# USB.net
KiCad netlist of a schematic drawn in Altium Designer
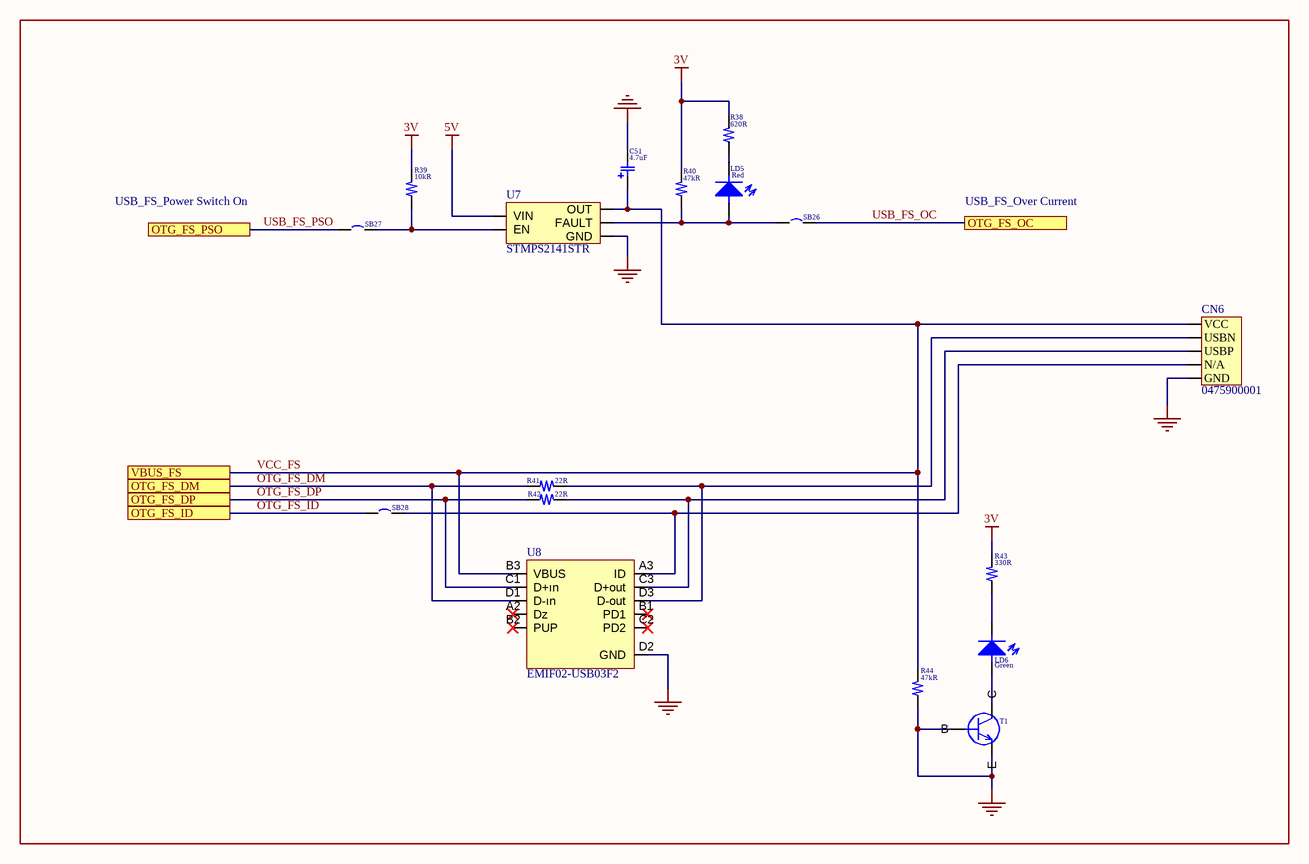
[diagram p0: USB.SchDoc]

(export (version "E")
  (design (tool "Eeschema 10.0.6"))
  (components
    (comp (ref "C51")
      (value "4.7uF")
      (footprint "CAP-TANT")
      (description "Cap Tant Polymer 4.7uF 10V K CASE 20% (3.2 x 1.6 x 1mm) SMD 300m Ohm 105°C T/R")
      (fields
        (field (name "MANUFACTURER") "Kyocera AVX")
        (field (name "MANUFACTURER PART NUMBER") "TCJK475M010R0300E")
      )
      (libsource (lib "STM32") (part "C-TANT POLY 4.7UF 10V 1206"))
    )
    (comp (ref "CN6")
      (value "0475900001")
      (footprint "USB MİCRO A")
      (description "USB Connector, 5 Contact(s), Female, Right Angle, Surface Mount Terminal, Locking, Receptacle")
      (fields (field (name "MANUFACTURER") "Molex") (field (name "MANUFACTURER PART NUMBER") "47590-0001"))
      (libsource (lib "STM32") (part "CONN USB MİCRO A 5P"))
    )
    (comp (ref "LD5")
      (value "150060RS75000")
      (footprint "LED-RED-0603")
      (description "LED Low-Power Uni-Color Red 630nm 2V 2-Pin Chip 0603(1608Metric) T/R")
      (fields (field (name "MANUFACTURER") "Wurth Electronics") (field (name "COLOR") "Red"))
      (libsource (lib "STM32") (part "LED RED CLEAR 0603 SMD"))
    )
    (comp (ref "LD6")
      (value "150060VS75000")
      (footprint "LED-GREEN-0603")
      (description "WURTH ELEKTRONIK - 150060VS75000 - LED, Green, SMD, 0603, 30 mA, 2 V, 570 nm")
      (fields (field (name "MANUFACTURER") "Wurth Electronics") (field (name "COLOR") "Green"))
      (libsource (lib "STM32") (part "LED GREEN CLEAR 0603 SMD"))
    )
    (comp (ref "R38")
      (value "620R")
      (footprint "RES-0603")
      (description "SMD Chip Resistor, 620 Ohm, ± 1%, 100 mW, 0603 [1608 Metric], Thick Film, General Purpose")
      (fields
        (field (name "MANUFACTURER") "Yageo")
        (field (name "MANUFACTURER PART NUMBER") "RC0603FR-07620RL")
      )
      (libsource (lib "STM32") (part "RES 620 OHM 1% 1/10W 0603"))
    )
    (comp (ref "R39")
      (value "10kR")
      (footprint "RES-0402")
      (description "SMD Chip Resistor, 10 kOhm, ± 1%, 63 mW, 0402 [1005 Metric], Thick Film, General Purpose")
      (fields
        (field (name "MANUFACTURER") "Yageo")
        (field (name "MANUFACTURER PART NUMBER") "RC0402FR-0710KL")
      )
      (libsource (lib "STM32") (part "RES 10K OHM 1% 1/16W 0402"))
    )
    (comp (ref "R40")
      (value "47kR")
      (footprint "RES-0402")
      (description "SMD Chip Resistor, 47 kOhm, ± 1%, 63 mW, 0402 [1005 Metric], Thick Film, General Purpose")
      (fields
        (field (name "MANUFACTURER") "Yageo")
        (field (name "MANUFACTURER PART NUMBER") "RC0402FR-0747KL")
      )
      (libsource (lib "STM32") (part "RES 47K OHM 1% 1/16W 0402"))
    )
    (comp (ref "R41")
      (value "22R")
      (footprint "RES-0603")
      (description "SMD Chip Resistor, 22 Ohm, ± 1%, 100 mW, 0603 [1608 Metric], Thick Film, General Purpose")
      (fields
        (field (name "MANUFACTURER") "Yageo")
        (field (name "MANUFACTURER PART NUMBER") "RC0603FR-0722RL")
      )
      (libsource (lib "STM32") (part "RES 22 OHM 1% 1/10W 0603"))
    )
    (comp (ref "R42")
      (value "22R")
      (footprint "RES-0603")
      (description "SMD Chip Resistor, 22 Ohm, ± 1%, 100 mW, 0603 [1608 Metric], Thick Film, General Purpose")
      (fields
        (field (name "MANUFACTURER") "Yageo")
        (field (name "MANUFACTURER PART NUMBER") "RC0603FR-0722RL")
      )
      (libsource (lib "STM32") (part "RES 22 OHM 1% 1/10W 0603"))
    )
    (comp (ref "R43")
      (value "330R")
      (footprint "RES-0402")
      (description "SMD Chip Resistor, 330 Ohm, ± 1%, 63 mW, 0402 [1005 Metric], Thick Film, General Purpose")
      (fields
        (field (name "MANUFACTURER") "Yageo")
        (field (name "MANUFACTURER PART NUMBER") "RC0402FR-07330RL")
      )
      (libsource (lib "STM32") (part "RES 330 OHM 1% 1/16W 0402"))
    )
    (comp (ref "R44")
      (value "47kR")
      (footprint "RES-0402")
      (description "SMD Chip Resistor, 47 kOhm, ± 1%, 63 mW, 0402 [1005 Metric], Thick Film, General Purpose")
      (fields
        (field (name "MANUFACTURER") "Yageo")
        (field (name "MANUFACTURER PART NUMBER") "RC0402FR-0747KL")
      )
      (libsource (lib "STM32") (part "RES 47K OHM 1% 1/16W 0402"))
    )
    (comp (ref "SB26")
      (value "RC0402JR-070RL")
      (footprint "RES-0402")
      (description "Zero Ohm Resistor, Jumper, 0402 [1005 Metric], Thick Film, 62.5 mW, 1 A, Surface Mount")
      (fields
        (field (name "MANUFACTURER") "Yageo")
        (field (name "MANUFACTURER PART NUMBER") "RC0603JR-070RL")
      )
      (libsource (lib "STM32") (part "RES 0 OHM JUMPER 1/10W 0603"))
    )
    (comp (ref "SB27")
      (value "RC0402JR-070RL")
      (footprint "RES-0402")
      (description "Zero Ohm Resistor, Jumper, 0402 [1005 Metric], Thick Film, 62.5 mW, 1 A, Surface Mount")
      (fields
        (field (name "MANUFACTURER") "Yageo")
        (field (name "MANUFACTURER PART NUMBER") "RC0603JR-070RL")
      )
      (libsource (lib "STM32") (part "RES 0 OHM JUMPER 1/10W 0603"))
    )
    (comp (ref "SB28")
      (value "RC0402JR-070RL")
      (footprint "RES-0402")
      (description "Zero Ohm Resistor, Jumper, 0402 [1005 Metric], Thick Film, 62.5 mW, 1 A, Surface Mount")
      (fields
        (field (name "MANUFACTURER") "Yageo")
        (field (name "MANUFACTURER PART NUMBER") "RC0603JR-070RL")
      )
      (libsource (lib "STM32") (part "RES 0 OHM JUMPER 1/10W 0603"))
    )
    (comp (ref "T1")
      (value "MMBT2222ALT1G")
      (footprint "SOT23-3")
      (description "Bipolar (BJT) Transistor NPN 40V 600mA 300MHz 225mW Surface Mount SOT-23-3")
      (fields (field (name "MANUFACTURER") "ON Semiconductor"))
      (libsource (lib "STM32") (part "TRANS NPN 40V 0.6A SOT23-3"))
    )
    (comp (ref "U7")
      (value "STMPS2141STR")
      (footprint "SOT23-5L")
      (description "STMPS Series 1 Channel 5.5 V 500 mA 200 mOhm High Side Power Switch - SOT-23-5")
      (fields (field (name "MANUFACTURER") "STMicroelectronics"))
      (libsource (lib "STM32") (part "IC PWR SWITCH N-CHAN 1{colon}1 SOT23-5"))
    )
    (comp (ref "U8")
      (value "EMIF02-USB03F2")
      (footprint "Flip-Chip-11")
      (description "2-line EMI filter and ESD protection with R pull-up for USB interfaces")
      (fields (field (name "MANUFACTURER") "STMicroelectronics"))
      (libsource (lib "STM32") (part "FILTER RC(PI) 33 OHM/20PF SMD"))
    )
  )
  (nets
    (net (code "1") (name "/OTG_FS_DM") (class "Default")
      (node (ref "R41") (pin "1") (pinfunction "1_1") (pintype "passive"))
      (node (ref "U8") (pin "D1") (pinfunction "D-ın_D1") (pintype "passive"))
    )
    (net (code "2") (name "/OTG_FS_DP") (class "Default")
      (node (ref "R42") (pin "1") (pinfunction "1_1") (pintype "passive"))
      (node (ref "U8") (pin "C1") (pinfunction "D+ın_C1") (pintype "passive"))
    )
    (net (code "3") (name "/OTG_FS_ID") (class "Default")
      (node (ref "SB28") (pin "1") (pinfunction "1_1") (pintype "passive"))
    )
    (net (code "4") (name "/USB_FS_OC") (class "Default")
      (node (ref "SB26") (pin "2") (pinfunction "2_2") (pintype "passive"))
    )
    (net (code "5") (name "/USB_FS_PSO") (class "Default")
      (node (ref "SB27") (pin "1") (pinfunction "1_1") (pintype "passive"))
    )
    (net (code "6") (name "/VCC_FS") (class "Default")
      (node (ref "C51") (pin "1") (pinfunction "1_1") (pintype "passive"))
      (node (ref "CN6") (pin "1") (pinfunction "VCC_1") (pintype "passive"))
      (node (ref "R44") (pin "2") (pinfunction "2_2") (pintype "passive"))
      (node (ref "U7") (pin "1") (pinfunction "OUT_1") (pintype "passive"))
      (node (ref "U8") (pin "B3") (pinfunction "VBUS_B3") (pintype "passive"))
    )
    (net (code "7") (name "3V") (class "Default")
      (node (ref "R38") (pin "2") (pinfunction "2_2") (pintype "passive"))
      (node (ref "R39") (pin "2") (pinfunction "2_2") (pintype "passive"))
      (node (ref "R40") (pin "2") (pinfunction "2_2") (pintype "passive"))
      (node (ref "R43") (pin "2") (pinfunction "2_2") (pintype "passive"))
    )
    (net (code "8") (name "5V") (class "Default")
      (node (ref "U7") (pin "5") (pinfunction "VIN_5") (pintype "passive"))
    )
    (net (code "9") (name "GND") (class "Default")
      (node (ref "C51") (pin "2") (pinfunction "2_2") (pintype "passive"))
      (node (ref "CN6") (pin "5") (pinfunction "GND_5") (pintype "passive"))
      (node (ref "R44") (pin "1") (pinfunction "1_1") (pintype "passive"))
      (node (ref "T1") (pin "1") (pinfunction "B_1") (pintype "passive"))
      (node (ref "T1") (pin "2") (pinfunction "E_2") (pintype "passive"))
      (node (ref "U7") (pin "2") (pinfunction "GND_2") (pintype "passive"))
      (node (ref "U8") (pin "D2") (pinfunction "GND_D2") (pintype "passive"))
    )
    (net (code "10") (name "Net-(CN6-N{slash}A)") (class "Default")
      (node (ref "CN6") (pin "4") (pinfunction "N/A_4") (pintype "passive"))
      (node (ref "SB28") (pin "2") (pinfunction "2_2") (pintype "passive"))
      (node (ref "U8") (pin "A3") (pinfunction "ID_A3") (pintype "passive"))
    )
    (net (code "11") (name "Net-(CN6-USBN)") (class "Default")
      (node (ref "CN6") (pin "2") (pinfunction "USBN_2") (pintype "passive"))
      (node (ref "R41") (pin "2") (pinfunction "2_2") (pintype "passive"))
      (node (ref "U8") (pin "D3") (pinfunction "D-out_D3") (pintype "passive"))
    )
    (net (code "12") (name "Net-(CN6-USBP)") (class "Default")
      (node (ref "CN6") (pin "3") (pinfunction "USBP_3") (pintype "passive"))
      (node (ref "R42") (pin "2") (pinfunction "2_2") (pintype "passive"))
      (node (ref "U8") (pin "C3") (pinfunction "D+out_C3") (pintype "passive"))
    )
    (net (code "13") (name "Net-(LD5-Pad1)") (class "Default")
      (node (ref "LD5") (pin "1") (pinfunction "1_1") (pintype "passive"))
      (node (ref "R38") (pin "1") (pinfunction "1_1") (pintype "passive"))
    )
    (net (code "14") (name "Net-(LD6-Pad1)") (class "Default")
      (node (ref "LD6") (pin "1") (pinfunction "1_1") (pintype "passive"))
      (node (ref "R43") (pin "1") (pinfunction "1_1") (pintype "passive"))
    )
    (net (code "15") (name "Net-(T1-C)") (class "Default")
      (node (ref "LD6") (pin "2") (pinfunction "2_2") (pintype "passive"))
      (node (ref "T1") (pin "3") (pinfunction "C_3") (pintype "passive"))
    )
    (net (code "16") (name "Net-(U7-EN)") (class "Default")
      (node (ref "R39") (pin "1") (pinfunction "1_1") (pintype "passive"))
      (node (ref "SB27") (pin "2") (pinfunction "2_2") (pintype "passive"))
      (node (ref "U7") (pin "4") (pinfunction "EN_4") (pintype "passive"))
    )
    (net (code "17") (name "Net-(U7-FAULT)") (class "Default")
      (node (ref "LD5") (pin "2") (pinfunction "2_2") (pintype "passive"))
      (node (ref "R40") (pin "1") (pinfunction "1_1") (pintype "passive"))
      (node (ref "SB26") (pin "1") (pinfunction "1_1") (pintype "passive"))
      (node (ref "U7") (pin "3") (pinfunction "FAULT_3") (pintype "passive"))
    )
    (net (code "18") (name "unconnected-(U8-Dz-PadA2)") (class "Default")
      (node (ref "U8") (pin "A2") (pinfunction "Dz_A2") (pintype "passive+no_connect"))
    )
    (net (code "19") (name "unconnected-(U8-PD1-PadB1)") (class "Default")
      (node (ref "U8") (pin "B1") (pinfunction "PD1_B1") (pintype "passive+no_connect"))
    )
    (net (code "20") (name "unconnected-(U8-PD2-PadC2)") (class "Default")
      (node (ref "U8") (pin "C2") (pinfunction "PD2_C2") (pintype "passive+no_connect"))
    )
    (net (code "21") (name "unconnected-(U8-PUP-PadB2)") (class "Default")
      (node (ref "U8") (pin "B2") (pinfunction "PUP_B2") (pintype "passive+no_connect"))
    )
  )
)
